# example_3_AMmodulation.net
KiCad netlist of a schematic drawn in EAGLE
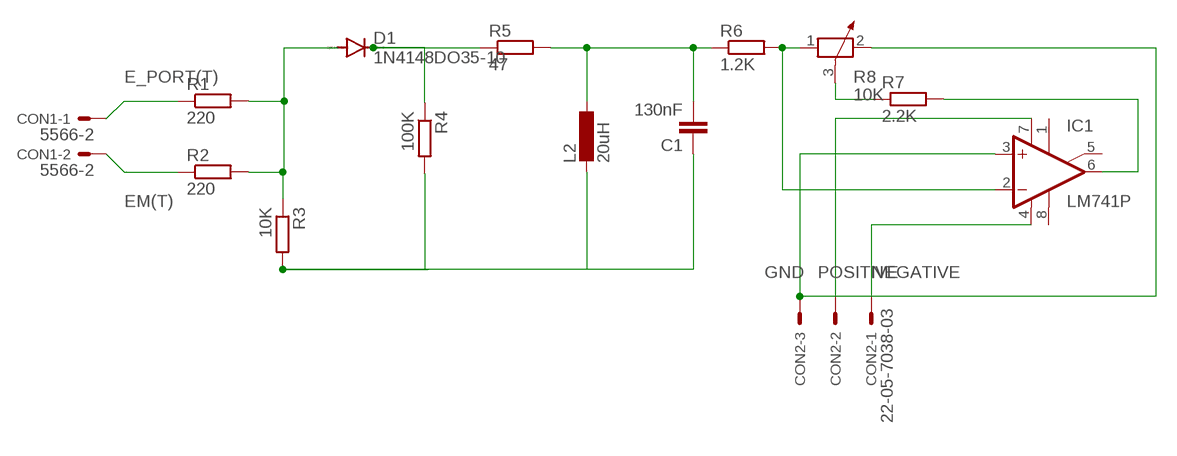
[diagram p0: schematic, sheet 1]

(export (version "E")
  (design (tool "Eeschema 10.0.6"))
  (components
    (comp (ref "C1")
      (value "130nF")
      (footprint "eagle-import:C025-025X050")
      (libsource (lib "eagle-import") (part "C-EU025-025X050"))
    )
    (comp (ref "CON1")
      (value "5566-2")
      (footprint "eagle-import:5566-2")
      (fields (field (name "MF") "MOLEX"))
      (libsource (lib "eagle-import") (part "5566-2"))
    )
    (comp (ref "CON2")
      (value "22-05-7038-03")
      (footprint "eagle-import:7395-03")
      (fields (field (name "MF") "MOLEX"))
      (libsource (lib "eagle-import") (part "22-?-0305-7038"))
    )
    (comp (ref "D1")
      (value "1N4148DO35-10")
      (footprint "eagle-import:DO35-10")
      (libsource (lib "eagle-import") (part "1N4148DO35-10"))
    )
    (comp (ref "IC1")
      (value "LM741P")
      (footprint "eagle-import:DIL08")
      (libsource (lib "eagle-import") (part "741PLM"))
    )
    (comp (ref "L2")
      (value "20uH")
      (footprint "eagle-import:0204_7")
      (libsource (lib "eagle-import") (part "L-EU0204/7"))
    )
    (comp (ref "R1")
      (value "220")
      (footprint "eagle-import:0204_7")
      (libsource (lib "eagle-import") (part "R-EU_0204/7"))
    )
    (comp (ref "R2")
      (value "220")
      (footprint "eagle-import:0204_7")
      (libsource (lib "eagle-import") (part "R-EU_0204/7"))
    )
    (comp (ref "R3")
      (value "10K")
      (footprint "eagle-import:0204_7")
      (libsource (lib "eagle-import") (part "R-EU_0204/7"))
    )
    (comp (ref "R4")
      (value "100K")
      (footprint "eagle-import:0204_7")
      (libsource (lib "eagle-import") (part "R-EU_0204/7"))
    )
    (comp (ref "R5")
      (value "47")
      (footprint "eagle-import:0204_7")
      (libsource (lib "eagle-import") (part "R-EU_0204/7"))
    )
    (comp (ref "R6")
      (value "1.2K")
      (footprint "eagle-import:0204_7")
      (libsource (lib "eagle-import") (part "R-EU_0204/7"))
    )
    (comp (ref "R7")
      (value "2.2K")
      (footprint "eagle-import:0204_7")
      (libsource (lib "eagle-import") (part "R-EU_0204/7"))
    )
    (comp (ref "R8")
      (value "10K")
      (footprint "eagle-import:PT-10")
      (libsource (lib "eagle-import") (part "POTENTIOMETER_PT-10"))
    )
  )
  (nets
    (net (code "1") (name "/EM(T)") (class "Default")
      (node (ref "CON1") (pin "2") (pinfunction "S_2") (pintype "passive"))
      (node (ref "R2") (pin "1") (pinfunction "1_1") (pintype "passive"))
    )
    (net (code "2") (name "/E_PORT(T)") (class "Default")
      (node (ref "CON1") (pin "1") (pinfunction "S_1") (pintype "passive"))
      (node (ref "R1") (pin "1") (pinfunction "1_1") (pintype "passive"))
    )
    (net (code "3") (name "/GND") (class "Default")
      (node (ref "CON2") (pin "3") (pinfunction "S_3") (pintype "passive"))
      (node (ref "IC1") (pin "3") (pinfunction "+IN_3") (pintype "input"))
      (node (ref "R8") (pin "2") (pinfunction "2_2") (pintype "passive"))
    )
    (net (code "4") (name "/NEGATIVE") (class "Default")
      (node (ref "CON2") (pin "1") (pinfunction "S_1") (pintype "passive"))
      (node (ref "IC1") (pin "4") (pinfunction "V-_4") (pintype "power_in"))
    )
    (net (code "5") (name "/POSITIVE") (class "Default")
      (node (ref "CON2") (pin "2") (pinfunction "S_2") (pintype "passive"))
      (node (ref "IC1") (pin "7") (pinfunction "V+_7") (pintype "power_in"))
    )
    (net (code "6") (name "Net-(C1-Pad1)") (class "Default")
      (node (ref "C1") (pin "1") (pinfunction "1_1") (pintype "passive"))
      (node (ref "L2") (pin "2") (pinfunction "2_2") (pintype "passive"))
      (node (ref "R3") (pin "2") (pinfunction "2_2") (pintype "passive"))
      (node (ref "R4") (pin "2") (pinfunction "2_2") (pintype "passive"))
    )
    (net (code "7") (name "Net-(C1-Pad2)") (class "Default")
      (node (ref "C1") (pin "2") (pinfunction "2_2") (pintype "passive"))
      (node (ref "L2") (pin "1") (pinfunction "1_1") (pintype "passive"))
      (node (ref "R5") (pin "2") (pinfunction "2_2") (pintype "passive"))
      (node (ref "R6") (pin "1") (pinfunction "1_1") (pintype "passive"))
    )
    (net (code "8") (name "Net-(D1-PadA)") (class "Default")
      (node (ref "D1") (pin "A") (pinfunction "A_A") (pintype "passive"))
      (node (ref "R1") (pin "2") (pinfunction "2_2") (pintype "passive"))
      (node (ref "R2") (pin "2") (pinfunction "2_2") (pintype "passive"))
      (node (ref "R3") (pin "1") (pinfunction "1_1") (pintype "passive"))
    )
    (net (code "9") (name "Net-(D1-PadC)") (class "Default")
      (node (ref "D1") (pin "C") (pinfunction "C_C") (pintype "passive"))
      (node (ref "R4") (pin "1") (pinfunction "1_1") (pintype "passive"))
      (node (ref "R5") (pin "1") (pinfunction "1_1") (pintype "passive"))
    )
    (net (code "10") (name "Net-(IC1--IN)") (class "Default")
      (node (ref "IC1") (pin "2") (pinfunction "-IN_2") (pintype "input"))
      (node (ref "R6") (pin "2") (pinfunction "2_2") (pintype "passive"))
      (node (ref "R8") (pin "1") (pinfunction "1_1") (pintype "passive"))
    )
    (net (code "11") (name "Net-(IC1-OUT)") (class "Default")
      (node (ref "IC1") (pin "6") (pinfunction "OUT_6") (pintype "output"))
      (node (ref "R7") (pin "2") (pinfunction "2_2") (pintype "passive"))
    )
    (net (code "12") (name "Net-(R7-Pad1)") (class "Default")
      (node (ref "R7") (pin "1") (pinfunction "1_1") (pintype "passive"))
      (node (ref "R8") (pin "3") (pinfunction "3_3") (pintype "passive"))
    )
    (net (code "13") (name "unconnected-(IC1-ON1-Pad1)") (class "Default")
      (node (ref "IC1") (pin "1") (pinfunction "ON1_1") (pintype "passive"))
    )
    (net (code "14") (name "unconnected-(IC1-ON2-Pad5)") (class "Default")
      (node (ref "IC1") (pin "5") (pinfunction "ON2_5") (pintype "passive"))
    )
    (net (code "15") (name "unconnected-(IC1-OPT-Pad8)") (class "Default")
      (node (ref "IC1") (pin "8") (pinfunction "OPT_8") (pintype "passive"))
    )
  )
)
